# F407.net
KiCad netlist of a schematic drawn in Altium Designer
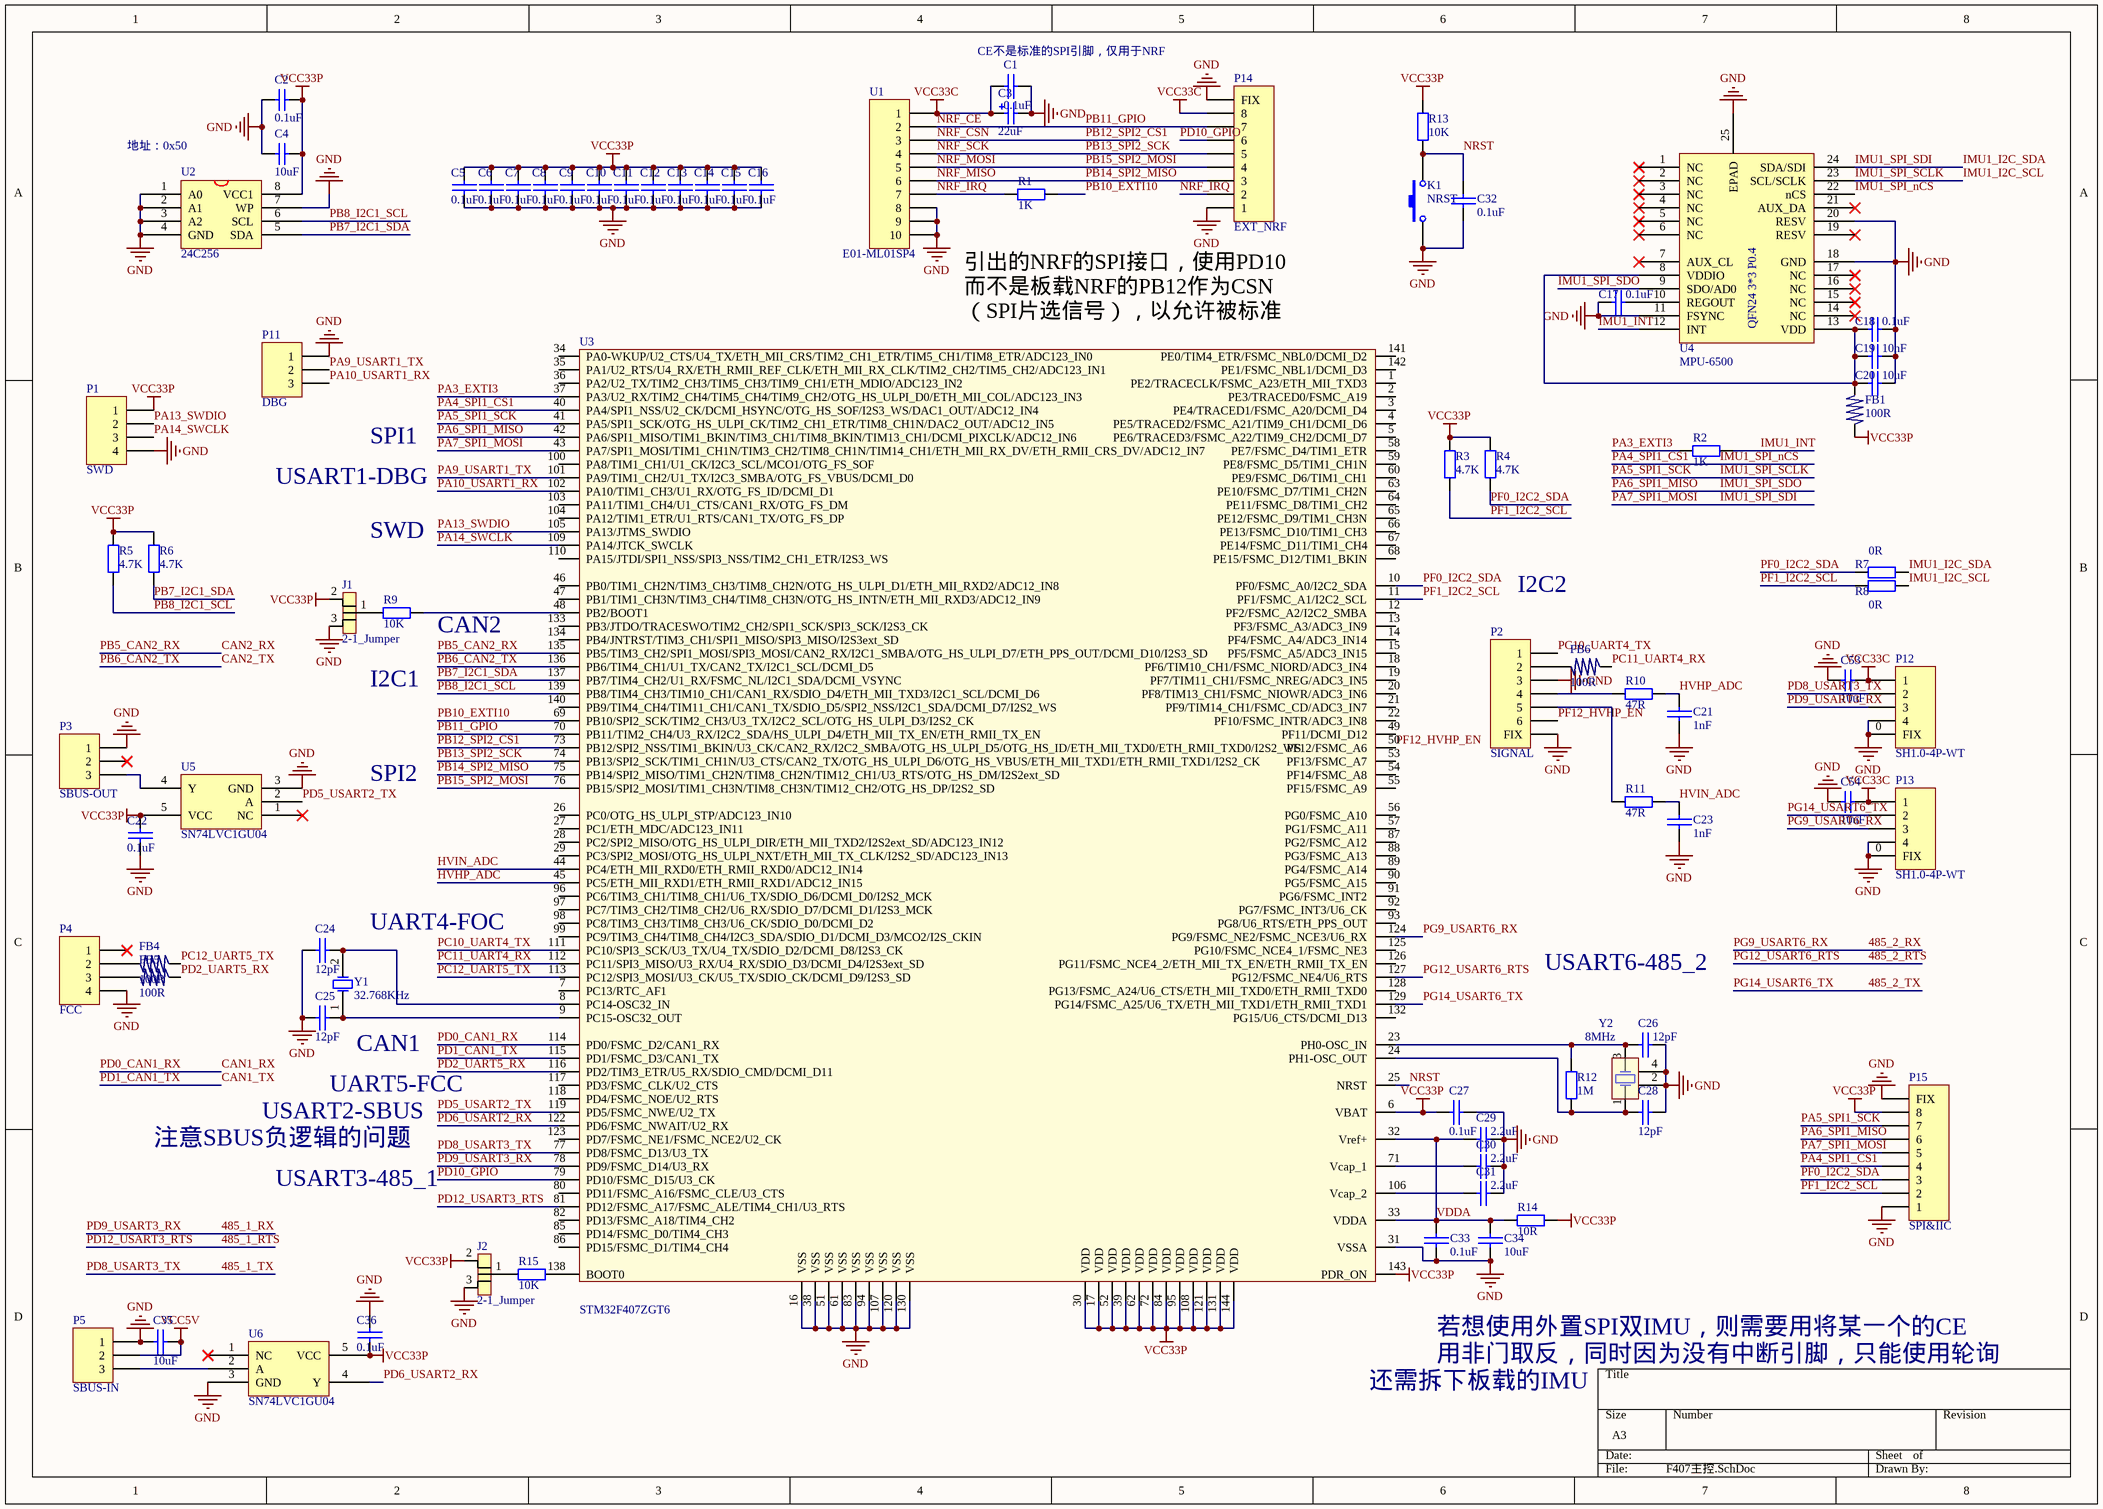
[diagram p0: F407主控.SchDoc]

(export (version "E")
  (design (tool "Eeschema 10.0.6"))
  (components
    (comp (ref "C1")
      (value "0.1uF")
      (footprint "C0805_M")
      (description "Capacitor")
      (libsource (lib "*") (part "CAP"))
    )
    (comp (ref "C2")
      (value "0.1uF")
      (footprint "C0805_M")
      (description "Capacitor")
      (fields (field (name "PUBLISHER") "Altium Limited"))
      (libsource (lib "Miscellaneous Devices") (part "Cap"))
    )
    (comp (ref "C3")
      (value "22uF")
      (footprint "CS 6*6 - R")
      (description "Polarized Capacitor (Axial)")
      (fields (field (name "PUBLISHER") "Altium Limited"))
      (libsource (lib "Miscellaneous Devices") (part "Cap Pol2"))
    )
    (comp (ref "C4")
      (value "10uF")
      (footprint "C0805_M")
      (description "Capacitor")
      (fields (field (name "PUBLISHER") "Altium Limited"))
      (libsource (lib "Miscellaneous Devices") (part "Cap"))
    )
    (comp (ref "C5")
      (value "0.1uF")
      (footprint "C0805_M")
      (description "Capacitor")
      (libsource (lib "*") (part "CAP"))
    )
    (comp (ref "C6")
      (value "0.1uF")
      (footprint "C0805_M")
      (description "Capacitor")
      (libsource (lib "*") (part "CAP"))
    )
    (comp (ref "C7")
      (value "0.1uF")
      (footprint "C0805_M")
      (description "Capacitor")
      (libsource (lib "*") (part "CAP"))
    )
    (comp (ref "C8")
      (value "0.1uF")
      (footprint "C0805_M")
      (description "Capacitor")
      (libsource (lib "*") (part "CAP"))
    )
    (comp (ref "C9")
      (value "0.1uF")
      (footprint "C0805_M")
      (description "Capacitor")
      (libsource (lib "*") (part "CAP"))
    )
    (comp (ref "C10")
      (value "0.1uF")
      (footprint "C0805_M")
      (description "Capacitor")
      (libsource (lib "*") (part "CAP"))
    )
    (comp (ref "C11")
      (value "0.1uF")
      (footprint "C0805_M")
      (description "Capacitor")
      (libsource (lib "*") (part "CAP"))
    )
    (comp (ref "C12")
      (value "0.1uF")
      (footprint "C0805_M")
      (description "Capacitor")
      (libsource (lib "*") (part "CAP"))
    )
    (comp (ref "C13")
      (value "0.1uF")
      (footprint "C0805_M")
      (description "Capacitor")
      (libsource (lib "*") (part "CAP"))
    )
    (comp (ref "C14")
      (value "0.1uF")
      (footprint "C0805_M")
      (description "Capacitor")
      (libsource (lib "*") (part "CAP"))
    )
    (comp (ref "C15")
      (value "0.1uF")
      (footprint "C0805_M")
      (description "Capacitor")
      (libsource (lib "*") (part "CAP"))
    )
    (comp (ref "C16")
      (value "0.1uF")
      (footprint "C0805_M")
      (description "Capacitor")
      (libsource (lib "*") (part "CAP"))
    )
    (comp (ref "C17")
      (value "0.1uF")
      (footprint "C0805_M")
      (description "Capacitor")
      (libsource (lib "*") (part "CAP"))
    )
    (comp (ref "C18")
      (value "0.1uF")
      (footprint "C0805_M")
      (description "Capacitor")
      (libsource (lib "*") (part "CAP"))
    )
    (comp (ref "C19")
      (value "10nF")
      (footprint "C0805_M")
      (description "Capacitor")
      (libsource (lib "*") (part "CAP"))
    )
    (comp (ref "C20")
      (value "10uF")
      (footprint "C0805_M")
      (description "Capacitor")
      (libsource (lib "*") (part "CAP"))
    )
    (comp (ref "C21")
      (value "1nF")
      (footprint "C0805_M")
      (description "Capacitor")
      (libsource (lib "*") (part "CAP"))
    )
    (comp (ref "C22")
      (value "0.1uF")
      (footprint "C0805_M")
      (description "Capacitor")
      (libsource (lib "*") (part "CAP"))
    )
    (comp (ref "C23")
      (value "1nF")
      (footprint "C0805_M")
      (description "Capacitor")
      (libsource (lib "*") (part "CAP"))
    )
    (comp (ref "C24")
      (value "12pF")
      (footprint "C0805_M")
      (description "Capacitor")
      (libsource (lib "*") (part "CAP"))
    )
    (comp (ref "C25")
      (value "12pF")
      (footprint "C0805_M")
      (description "Capacitor")
      (libsource (lib "*") (part "CAP"))
    )
    (comp (ref "C26")
      (value "12pF")
      (footprint "C0805_M")
      (description "Capacitor")
      (libsource (lib "*") (part "CAP"))
    )
    (comp (ref "C27")
      (value "0.1uF")
      (footprint "C0805_M")
      (description "Capacitor")
      (libsource (lib "*") (part "CAP"))
    )
    (comp (ref "C28")
      (value "12pF")
      (footprint "C0805_M")
      (description "Capacitor")
      (libsource (lib "*") (part "CAP"))
    )
    (comp (ref "C29")
      (value "2.2uF")
      (footprint "C0805_M")
      (description "Capacitor")
      (libsource (lib "*") (part "CAP"))
    )
    (comp (ref "C30")
      (value "2.2uF")
      (footprint "C0805_M")
      (description "Capacitor")
      (libsource (lib "*") (part "CAP"))
    )
    (comp (ref "C31")
      (value "2.2uF")
      (footprint "C0805_M")
      (description "Capacitor")
      (libsource (lib "*") (part "CAP"))
    )
    (comp (ref "C32")
      (value "0.1uF")
      (footprint "C0805_M")
      (description "Capacitor")
      (libsource (lib "*") (part "CAP"))
    )
    (comp (ref "C33")
      (value "0.1uF")
      (footprint "C0805_M")
      (description "Capacitor")
      (libsource (lib "*") (part "CAP"))
    )
    (comp (ref "C34")
      (value "10uF")
      (footprint "C0805_M")
      (description "Capacitor")
      (libsource (lib "*") (part "CAP"))
    )
    (comp (ref "C35")
      (value "10uF")
      (footprint "C0805_M")
      (description "Capacitor")
      (libsource (lib "*") (part "CAP"))
    )
    (comp (ref "C36")
      (value "0.1uF")
      (footprint "C0805_M")
      (description "Capacitor")
      (libsource (lib "*") (part "CAP"))
    )
    (comp (ref "C53")
      (value "10uF")
      (footprint "C0805_M")
      (description "Capacitor")
      (fields (field (name "PUBLISHER") "Altium Limited"))
      (libsource (lib "Miscellaneous Devices") (part "Cap"))
    )
    (comp (ref "C54")
      (value "10uF")
      (footprint "C0805_M")
      (description "Capacitor")
      (fields (field (name "PUBLISHER") "Altium Limited"))
      (libsource (lib "Miscellaneous Devices") (part "Cap"))
    )
    (comp (ref "FB1") (value "100R") (footprint "R0805_M") (libsource (lib "EXPLORER") (part "L")))
    (comp (ref "FB4") (value "100R") (footprint "R0805_M") (libsource (lib "") (part "L_1")))
    (comp (ref "FB5") (value "100R") (footprint "R0805_M") (libsource (lib "") (part "L_1")))
    (comp (ref "FB6") (value "100R") (footprint "R0805_M") (libsource (lib "") (part "L_1")))
    (comp (ref "J1")
      (value "2-1_Jumper")
      (footprint "2-1_Jumper")
      (libsource (lib "XL6005") (part "2-1_Jumper"))
    )
    (comp (ref "J2")
      (value "2-1_Jumper")
      (footprint "2-1_Jumper")
      (libsource (lib "XL6005") (part "2-1_Jumper"))
    )
    (comp (ref "K1")
      (value "NRST")
      (footprint "SW_SMT")
      (description "Switch")
      (fields (field (name "PUBLISHER") "Altium Limited"))
      (libsource (lib "Miscellaneous Devices") (part "SW-PB"))
    )
    (comp (ref "P1")
      (value "SWD")
      (footprint "XH2.54-LI-4P")
      (description "Header, 4-Pin")
      (fields (field (name "PUBLISHER") "Altium Limited"))
      (libsource (lib "Miscellaneous Connectors") (part "Header 4"))
    )
    (comp (ref "P2")
      (value "SIGNAL")
      (footprint "SH1.0-LT-6P")
      (description "Header, 7-Pin")
      (fields (field (name "PUBLISHER") "Altium Limited"))
      (libsource (lib "Miscellaneous Connectors") (part "Header 7"))
    )
    (comp (ref "P3")
      (value "SBUS-OUT")
      (footprint "XH2.54-LI-3P")
      (description "Header, 3-Pin")
      (fields (field (name "PUBLISHER") "Altium Limited"))
      (libsource (lib "Miscellaneous Connectors") (part "Header 3"))
    )
    (comp (ref "P4")
      (value "FCC")
      (footprint "XH2.54-LI-4P")
      (description "Header, 4-Pin")
      (fields (field (name "PUBLISHER") "Altium Limited"))
      (libsource (lib "Miscellaneous Connectors") (part "Header 4"))
    )
    (comp (ref "P5")
      (value "SBUS-IN")
      (footprint "XH2.54-LI-3P")
      (description "Header, 3-Pin")
      (fields (field (name "PUBLISHER") "Altium Limited"))
      (libsource (lib "Miscellaneous Connectors") (part "Header 3"))
    )
    (comp (ref "P11")
      (value "DBG")
      (footprint "XH2.54-LI-3P")
      (description "Header, 3-Pin")
      (fields (field (name "PUBLISHER") "Altium Limited"))
      (libsource (lib "Miscellaneous Connectors") (part "Header 3"))
    )
    (comp (ref "P12")
      (value "SH1.0-4P-WT")
      (footprint "SH1.0-WT-4P")
      (description "Header, 5-Pin")
      (fields (field (name "PUBLISHER") "Altium Limited"))
      (libsource (lib "Miscellaneous Connectors") (part "Header 5"))
    )
    (comp (ref "P13")
      (value "SH1.0-4P-WT")
      (footprint "SH1.0-WT-4P")
      (description "Header, 5-Pin")
      (fields (field (name "PUBLISHER") "Altium Limited"))
      (libsource (lib "Miscellaneous Connectors") (part "Header 5"))
    )
    (comp (ref "P14")
      (value "EXT_NRF")
      (footprint "SH1.0-WT-8P")
      (description "Header, 9-Pin")
      (fields (field (name "PUBLISHER") "Altium Limited"))
      (libsource (lib "Miscellaneous Connectors") (part "Header 9"))
    )
    (comp (ref "P15")
      (value "SPI&IIC")
      (footprint "SH1.0-WT-8P")
      (description "Header, 9-Pin")
      (fields (field (name "PUBLISHER") "Altium Limited"))
      (libsource (lib "Miscellaneous Connectors") (part "Header 9"))
    )
    (comp (ref "R1")
      (value "1K")
      (footprint "R0805_M")
      (description "Resistor")
      (fields (field (name "PUBLISHER") "Altium Limited"))
      (libsource (lib "") (part "Res2_1"))
    )
    (comp (ref "R2")
      (value "1K")
      (footprint "R0805_M")
      (description "Resistor")
      (fields (field (name "PUBLISHER") "Altium Limited"))
      (libsource (lib "") (part "Res2_1"))
    )
    (comp (ref "R3")
      (value "4.7K")
      (footprint "R0805_M")
      (description "Resistor")
      (fields (field (name "PUBLISHER") "Altium Limited"))
      (libsource (lib "") (part "Res2_2"))
    )
    (comp (ref "R4")
      (value "4.7K")
      (footprint "R0805_M")
      (description "Resistor")
      (fields (field (name "PUBLISHER") "Altium Limited"))
      (libsource (lib "") (part "Res2_2"))
    )
    (comp (ref "R5")
      (value "4.7K")
      (footprint "R0805_M")
      (description "Resistor")
      (fields (field (name "PUBLISHER") "Altium Limited"))
      (libsource (lib "") (part "Res2_2"))
    )
    (comp (ref "R6")
      (value "4.7K")
      (footprint "R0805_M")
      (description "Resistor")
      (fields (field (name "PUBLISHER") "Altium Limited"))
      (libsource (lib "") (part "Res2_2"))
    )
    (comp (ref "R7")
      (value "0R")
      (footprint "R0805_M")
      (description "Resistor")
      (fields (field (name "PUBLISHER") "Altium Limited"))
      (libsource (lib "") (part "Res2_1"))
    )
    (comp (ref "R8")
      (value "0R")
      (footprint "R0805_M")
      (description "Resistor")
      (fields (field (name "PUBLISHER") "Altium Limited"))
      (libsource (lib "") (part "Res2_1"))
    )
    (comp (ref "R9")
      (value "10K")
      (footprint "R0805_M")
      (description "Resistor")
      (fields (field (name "PUBLISHER") "Altium Limited"))
      (libsource (lib "") (part "Res2_1"))
    )
    (comp (ref "R10")
      (value "47R")
      (footprint "R0805_M")
      (description "Resistor")
      (fields (field (name "PUBLISHER") "Altium Limited"))
      (libsource (lib "Miscellaneous Devices") (part "Res2"))
    )
    (comp (ref "R11")
      (value "47R")
      (footprint "R0805_M")
      (description "Resistor")
      (fields (field (name "PUBLISHER") "Altium Limited"))
      (libsource (lib "Miscellaneous Devices") (part "Res2"))
    )
    (comp (ref "R12")
      (value "1M")
      (footprint "R0805_M")
      (description "Resistor")
      (fields (field (name "PUBLISHER") "Altium Limited"))
      (libsource (lib "") (part "Res2_3"))
    )
    (comp (ref "R13")
      (value "10K")
      (footprint "R0805_M")
      (description "Resistor")
      (fields (field (name "PUBLISHER") "Altium Limited"))
      (libsource (lib "") (part "Res2_2"))
    )
    (comp (ref "R14")
      (value "10R")
      (footprint "R0805_M")
      (description "Resistor")
      (fields (field (name "PUBLISHER") "Altium Limited"))
      (libsource (lib "") (part "Res2_1"))
    )
    (comp (ref "R15")
      (value "10K")
      (footprint "R0805_M")
      (description "Resistor")
      (fields (field (name "PUBLISHER") "Altium Limited"))
      (libsource (lib "") (part "Res2_1"))
    )
    (comp (ref "U1")
      (value "E01-ML01SP4")
      (footprint "PE01-ML01SP4")
      (description "Header, 10-Pin")
      (fields (field (name "PUBLISHER") "Altium Limited"))
      (libsource (lib "Miscellaneous Connectors") (part "Header 10"))
    )
    (comp (ref "U2")
      (value "24C256")
      (footprint "SOP-8")
      (libsource (lib "Explorer STM32F407封装库") (part "24C256"))
    )
    (comp (ref "U3")
      (value "STM32F407ZGT6")
      (footprint "2.12-矩形QFP封装:LQFP144")
      (description "STM32F407ZET6")
      (libsource (lib "EXPLORER") (part "STM32F407ZET6"))
    )
    (comp (ref "U4")
      (value "MPU-6500")
      (footprint "QFN24-L3.0-W3.0-P0.4")
      (description "6 DoF IMU Footprint QFN24 3*3 P0.4")
      (libsource (lib "XL6005") (part "MPU-6500"))
    )
    (comp (ref "U5")
      (value "SN74LVC1GU04")
      (footprint "SOT-23-5")
      (libsource (lib "") (part "SN74LVC1GU04_1"))
    )
    (comp (ref "U6")
      (value "SN74LVC1GU04")
      (footprint "SOT-23-5")
      (libsource (lib "7688A原理图封装") (part "SN74LVC1GU04"))
    )
    (comp (ref "Y1")
      (value "32.768KHz")
      (footprint "OSC-3215-2P")
      (description "CL=12.5pF")
      (fields (field (name "PUBLISHER") "Altium Limited"))
      (libsource (lib "Miscellaneous Devices") (part "XTAL"))
    )
    (comp (ref "Y2")
      (value "8MHz")
      (footprint "1.09-晶振、晶体:OSC-3225-4P")
      (description "CL=12pF")
      (fields (field (name "PUBLISHER") "Altium Limited"))
      (libsource (lib "XL6005") (part "XTAL-4"))
    )
  )
  (nets
    (net (code "1") (name "/485_1_RTS") (class "Default")
      (node (ref "U3") (pin "81") (pinfunction "PD12/FSMC_A17/FSMC_ALE/TIM4_CH1/U3_RTS_81") (pintype "passive"))
    )
    (net (code "2") (name "/485_1_RX") (class "Default")
      (node (ref "P12") (pin "3") (pinfunction "3_3") (pintype "passive"))
      (node (ref "U3") (pin "78") (pinfunction "PD9/FSMC_D14/U3_RX_78") (pintype "passive"))
    )
    (net (code "3") (name "/485_1_TX") (class "Default")
      (node (ref "P12") (pin "2") (pinfunction "2_2") (pintype "passive"))
      (node (ref "U3") (pin "77") (pinfunction "PD8/FSMC_D13/U3_TX_77") (pintype "passive"))
    )
    (net (code "4") (name "/485_2_RTS") (class "Default")
      (node (ref "U3") (pin "127") (pinfunction "PG12/FSMC_NE4/U6_RTS_127") (pintype "passive"))
    )
    (net (code "5") (name "/485_2_RX") (class "Default")
      (node (ref "P13") (pin "3") (pinfunction "3_3") (pintype "passive"))
      (node (ref "U3") (pin "124") (pinfunction "PG9/FSMC_NE2/FSMC_NCE3/U6_RX_124") (pintype "passive"))
    )
    (net (code "6") (name "/485_2_TX") (class "Default")
      (node (ref "P13") (pin "2") (pinfunction "2_2") (pintype "passive"))
      (node (ref "U3") (pin "129") (pinfunction "PG14/FSMC_A25/U6_TX/ETH_MII_TXD1/ETH_RMII_TXD1_129") (pintype "passive"))
    )
    (net (code "7") (name "/CAN1_RX") (class "Default")
      (node (ref "U3") (pin "114") (pinfunction "PD0/FSMC_D2/CAN1_RX_114") (pintype "passive"))
    )
    (net (code "8") (name "/CAN1_TX") (class "Default")
      (node (ref "U3") (pin "115") (pinfunction "PD1/FSMC_D3/CAN1_TX_115") (pintype "passive"))
    )
    (net (code "9") (name "/CAN2_RX") (class "Default")
      (node (ref "U3") (pin "135") (pinfunction "PB5/TIM3_CH2/SPI1_MOSI/SPI3_MOSI/CAN2_RX/I2C1_SMBA/OTG_HS_ULPI_D7/ETH_PPS_OUT/DCMI_D10/I2S3_SD_135") (pintype "passive"))
    )
    (net (code "10") (name "/CAN2_TX") (class "Default")
      (node (ref "U3") (pin "136") (pinfunction "PB6/TIM4_CH1/U1_TX/CAN2_TX/I2C1_SCL/DCMI_D5_136") (pintype "passive"))
    )
    (net (code "11") (name "/HVHP_ADC") (class "Default")
      (node (ref "C21") (pin "2") (pinfunction "2_2") (pintype "passive"))
      (node (ref "R10") (pin "2") (pinfunction "2_2") (pintype "passive"))
      (node (ref "U3") (pin "45") (pinfunction "PC5/ETH_MII_RXD1/ETH_RMII_RXD1/ADC12_IN15_45") (pintype "passive"))
    )
    (net (code "12") (name "/HVIN_ADC") (class "Default")
      (node (ref "C23") (pin "2") (pinfunction "2_2") (pintype "passive"))
      (node (ref "R11") (pin "2") (pinfunction "2_2") (pintype "passive"))
      (node (ref "U3") (pin "44") (pinfunction "PC4/ETH_MII_RXD0/ETH_RMII_RXD0/ADC12_IN14_44") (pintype "passive"))
    )
    (net (code "13") (name "/IMU1_I2C_SCL") (class "Default")
      (node (ref "P15") (pin "7") (pinfunction "7_7") (pintype "passive"))
      (node (ref "R8") (pin "1") (pinfunction "1_1") (pintype "passive"))
      (node (ref "U3") (pin "41") (pinfunction "PA5/SPI1_SCK/OTG_HS_ULPI_CK/TIM2_CH1_ETR/TIM8_CH1N/DAC2_OUT/ADC12_IN5_41") (pintype "passive"))
      (node (ref "U4") (pin "23") (pinfunction "SCL/SCLK_23") (pintype "passive"))
    )
    (net (code "14") (name "/IMU1_I2C_SDA") (class "Default")
      (node (ref "P15") (pin "5") (pinfunction "5_5") (pintype "passive"))
      (node (ref "R7") (pin "1") (pinfunction "1_1") (pintype "passive"))
      (node (ref "U3") (pin "43") (pinfunction "PA7/SPI1_MOSI/TIM1_CH1N/TIM3_CH2/TIM8_CH1N/TIM14_CH1/ETH_MII_RX_DV/ETH_RMII_CRS_DV/ADC12_IN7_43") (pintype "passive"))
      (node (ref "U4") (pin "24") (pinfunction "SDA/SDI_24") (pintype "passive"))
    )
    (net (code "15") (name "/IMU1_INT") (class "Default")
      (node (ref "R2") (pin "1") (pinfunction "1_1") (pintype "passive"))
      (node (ref "U4") (pin "12") (pinfunction "INT_12") (pintype "passive"))
    )
    (net (code "16") (name "/IMU1_SPI_SDO") (class "Default")
      (node (ref "P15") (pin "6") (pinfunction "6_6") (pintype "passive"))
      (node (ref "U3") (pin "42") (pinfunction "PA6/SPI1_MISO/TIM1_BKIN/TIM3_CH1/TIM8_BKIN/TIM13_CH1/DCMI_PIXCLK/ADC12_IN6_42") (pintype "passive"))
      (node (ref "U4") (pin "9") (pinfunction "SDO/AD0_9") (pintype "passive"))
    )
    (net (code "17") (name "/IMU1_SPI_nCS") (class "Default")
      (node (ref "P15") (pin "4") (pinfunction "4_4") (pintype "passive"))
      (node (ref "U3") (pin "40") (pinfunction "PA4/SPI1_NSS/U2_CK/DCMI_HSYNC/OTG_HS_SOF/I2S3_WS/DAC1_OUT/ADC12_IN4_40") (pintype "passive"))
      (node (ref "U4") (pin "22") (pinfunction "nCS_22") (pintype "passive"))
    )
    (net (code "18") (name "/NRF_CE") (class "Default")
      (node (ref "P14") (pin "7") (pinfunction "7_7") (pintype "passive"))
      (node (ref "U1") (pin "2") (pinfunction "2_2") (pintype "passive"))
      (node (ref "U3") (pin "70") (pinfunction "PB11/TIM2_CH4/U3_RX/I2C2_SDA/HS_ULPI_D4/ETH_MII_TX_EN/ETH_RMII_TX_EN_70") (pintype "passive"))
    )
    (net (code "19") (name "/NRF_CSN") (class "Default")
      (node (ref "U1") (pin "3") (pinfunction "3_3") (pintype "passive"))
      (node (ref "U3") (pin "73") (pinfunction "PB12/SPI2_NSS/TIM1_BKIN/U3_CK/CAN2_RX/I2C2_SMBA/OTG_HS_ULPI_D5/OTG_HS_ID/ETH_MII_TXD0/ETH_RMII_TXD0/I2S2_WS_73") (pintype "passive"))
    )
    (net (code "20") (name "/NRF_IRQ") (class "Default")
      (node (ref "P14") (pin "2") (pinfunction "2_2") (pintype "passive"))
      (node (ref "R1") (pin "2") (pinfunction "2_2") (pintype "passive"))
      (node (ref "U1") (pin "7") (pinfunction "7_7") (pintype "passive"))
    )
    (net (code "21") (name "/NRF_MISO") (class "Default")
      (node (ref "P14") (pin "3") (pinfunction "3_3") (pintype "passive"))
      (node (ref "U1") (pin "6") (pinfunction "6_6") (pintype "passive"))
      (node (ref "U3") (pin "75") (pinfunction "PB14/SPI2_MISO/TIM1_CH2N/TIM8_CH2N/TIM12_CH1/U3_RTS/OTG_HS_DM/I2S2ext_SD_75") (pintype "passive"))
    )
    (net (code "22") (name "/NRF_MOSI") (class "Default")
      (node (ref "P14") (pin "4") (pinfunction "4_4") (pintype "passive"))
      (node (ref "U1") (pin "5") (pinfunction "5_5") (pintype "passive"))
      (node (ref "U3") (pin "76") (pinfunction "PB15/SPI2_MOSI/TIM1_CH3N/TIM8_CH3N/TIM12_CH2/OTG_HS_DP/I2S2_SD_76") (pintype "passive"))
    )
    (net (code "23") (name "/NRF_SCK") (class "Default")
      (node (ref "P14") (pin "5") (pinfunction "5_5") (pintype "passive"))
      (node (ref "U1") (pin "4") (pinfunction "4_4") (pintype "passive"))
      (node (ref "U3") (pin "74") (pinfunction "PB13/SPI2_SCK/TIM1_CH1N/U3_CTS/CAN2_TX/OTG_HS_ULPI_D6/OTG_HS_VBUS/ETH_MII_TXD1/ETH_RMII_TXD1/I2S2_CK_74") (pintype "passive"))
    )
    (net (code "24") (name "/NRST") (class "Default")
      (node (ref "C32") (pin "2") (pinfunction "2_2") (pintype "passive"))
      (node (ref "K1") (pin "2") (pinfunction "2_2") (pintype "passive"))
      (node (ref "R13") (pin "2") (pinfunction "2_2") (pintype "passive"))
      (node (ref "U3") (pin "25") (pinfunction "NRST_25") (pintype "passive"))
    )
    (net (code "25") (name "/PA3_EXTI3") (class "Default")
      (node (ref "R2") (pin "2") (pinfunction "2_2") (pintype "passive"))
      (node (ref "U3") (pin "37") (pinfunction "PA3/U2_RX/TIM2_CH4/TIM5_CH4/TIM9_CH2/OTG_HS_ULPI_D0/ETH_MII_COL/ADC123_IN3_37") (pintype "passive"))
    )
    (net (code "26") (name "/PA9_USART1_TX") (class "Default")
      (node (ref "P11") (pin "2") (pinfunction "2_2") (pintype "passive"))
      (node (ref "U3") (pin "101") (pinfunction "PA9/TIM1_CH2/U1_TX/I2C3_SMBA/OTG_FS_VBUS/DCMI_D0_101") (pintype "passive"))
    )
    (net (code "27") (name "/PA10_USART1_RX") (class "Default")
      (node (ref "P11") (pin "3") (pinfunction "3_3") (pintype "passive"))
      (node (ref "U3") (pin "102") (pinfunction "PA10/TIM1_CH3/U1_RX/OTG_FS_ID/DCMI_D1_102") (pintype "passive"))
    )
    (net (code "28") (name "/PA13_SWDIO") (class "Default")
      (node (ref "P1") (pin "2") (pinfunction "2_2") (pintype "passive"))
      (node (ref "U3") (pin "105") (pinfunction "PA13/JTMS_SWDIO_105") (pintype "passive"))
    )
    (net (code "29") (name "/PA14_SWCLK") (class "Default")
      (node (ref "P1") (pin "3") (pinfunction "3_3") (pintype "passive"))
      (node (ref "U3") (pin "109") (pinfunction "PA14/JTCK_SWCLK_109") (pintype "passive"))
    )
    (net (code "30") (name "/PB7_I2C1_SDA") (class "Default")
      (node (ref "R6") (pin "2") (pinfunction "2_2") (pintype "passive"))
      (node (ref "U2") (pin "5") (pinfunction "SDA_5") (pintype "passive"))
      (node (ref "U3") (pin "137") (pinfunction "PB7/TIM4_CH2/U1_RX/FSMC_NL/I2C1_SDA/DCMI_VSYNC_137") (pintype "passive"))
    )
    (net (code "31") (name "/PB8_I2C1_SCL") (class "Default")
      (node (ref "R5") (pin "2") (pinfunction "2_2") (pintype "passive"))
      (node (ref "U2") (pin "6") (pinfunction "SCL_6") (pintype "passive"))
      (node (ref "U3") (pin "139") (pinfunction "PB8/TIM4_CH3/TIM10_CH1/CAN1_RX/SDIO_D4/ETH_MII_TXD3/I2C1_SCL/DCMI_D6_139") (pintype "passive"))
    )
    (net (code "32") (name "/PB10_EXTI10") (class "Default")
      (node (ref "R1") (pin "1") (pinfunction "1_1") (pintype "passive"))
      (node (ref "U3") (pin "69") (pinfunction "PB10/SPI2_SCK/TIM2_CH3/U3_TX/I2C2_SCL/OTG_HS_ULPI_D3/I2S2_CK_69") (pintype "passive"))
    )
    (net (code "33") (name "/PC10_UART4_TX") (class "Default")
      (node (ref "P2") (pin "1") (pinfunction "1_1") (pintype "passive"))
      (node (ref "U3") (pin "111") (pinfunction "PC10/SPI3_SCK/U3_TX/U4_TX/SDIO_D2/DCMI_D8/I2S3_CK_111") (pintype "passive"))
    )
    (net (code "34") (name "/PC11_UART4_RX") (class "Default")
      (node (ref "FB6") (pin "1") (pintype "passive"))
      (node (ref "U3") (pin "112") (pinfunction "PC11/SPI3_MISO/U3_RX/U4_RX/SDIO_D3/DCMI_D4/I2S3ext_SD_112") (pintype "passive"))
    )
    (net (code "35") (name "/PC12_UART5_TX") (class "Default")
      (node (ref "FB4") (pin "1") (pintype "passive"))
      (node (ref "U3") (pin "113") (pinfunction "PC12/SPI3_MOSI/U3_CK/U5_TX/SDIO_CK/DCMI_D9/I2S3_SD_113") (pintype "passive"))
    )
    (net (code "36") (name "/PD2_UART5_RX") (class "Default")
      (node (ref "FB5") (pin "1") (pintype "passive"))
      (node (ref "U3") (pin "116") (pinfunction "PD2/TIM3_ETR/U5_RX/SDIO_CMD/DCMI_D11_116") (pintype "passive"))
    )
    (net (code "37") (name "/PD5_USART2_TX") (class "Default")
      (node (ref "U3") (pin "119") (pinfunction "PD5/FSMC_NWE/U2_TX_119") (pintype "passive"))
      (node (ref "U5") (pin "2") (pinfunction "A_2") (pintype "passive"))
    )
    (net (code "38") (name "/PD6_USART2_RX") (class "Default")
      (node (ref "U3") (pin "122") (pinfunction "PD6/FSMC_NWAIT/U2_RX_122") (pintype "passive"))
      (node (ref "U6") (pin "4") (pinfunction "Y_4") (pintype "passive"))
    )
    (net (code "39") (name "/PD10_GPIO") (class "Default")
      (node (ref "P14") (pin "6") (pinfunction "6_6") (pintype "passive"))
      (node (ref "U3") (pin "79") (pinfunction "PD10/FSMC_D15/U3_CK_79") (pintype "passive"))
    )
    (net (code "40") (name "/PF0_I2C2_SDA") (class "Default")
      (node (ref "P15") (pin "3") (pinfunction "3_3") (pintype "passive"))
      (node (ref "R4") (pin "2") (pinfunction "2_2") (pintype "passive"))
      (node (ref "R7") (pin "2") (pinfunction "2_2") (pintype "passive"))
      (node (ref "U3") (pin "10") (pinfunction "PF0/FSMC_A0/I2C2_SDA_10") (pintype "passive"))
    )
    (net (code "41") (name "/PF1_I2C2_SCL") (class "Default")
      (node (ref "P15") (pin "2") (pinfunction "2_2") (pintype "passive"))
      (node (ref "R3") (pin "2") (pinfunction "2_2") (pintype "passive"))
      (node (ref "R8") (pin "2") (pinfunction "2_2") (pintype "passive"))
      (node (ref "U3") (pin "11") (pinfunction "PF1/FSMC_A1/I2C2_SCL_11") (pintype "passive"))
    )
    (net (code "42") (name "/PF12_HVHP_EN") (class "Default")
      (node (ref "P2") (pin "6") (pinfunction "6_6") (pintype "passive"))
      (node (ref "U3") (pin "50") (pinfunction "PF12/FSMC_A6_50") (pintype "passive"))
    )
    (net (code "43") (name "/VDDA") (class "Default")
      (node (ref "C29") (pin "1") (pinfunction "1_1") (pintype "passive"))
      (node (ref "C33") (pin "2") (pinfunction "2_2") (pintype "passive"))
      (node (ref "C34") (pin "2") (pinfunction "2_2") (pintype "passive"))
      (node (ref "R14") (pin "2") (pinfunction "2_2") (pintype "passive"))
      (node (ref "U3") (pin "32") (pinfunction "Vref+_32") (pintype "passive"))
      (node (ref "U3") (pin "33") (pinfunction "VDDA_33") (pintype "passive"))
    )
    (net (code "44") (name "GND") (class "Default")
      (node (ref "C1") (pin "1") (pinfunction "1_1") (pintype "passive"))
      (node (ref "C10") (pin "1") (pinfunction "1_1") (pintype "passive"))
      (node (ref "C11") (pin "1") (pinfunction "1_1") (pintype "passive"))
      (node (ref "C12") (pin "1") (pinfunction "1_1") (pintype "passive"))
      (node (ref "C13") (pin "1") (pinfunction "1_1") (pintype "passive"))
      (node (ref "C14") (pin "1") (pinfunction "1_1") (pintype "passive"))
      (node (ref "C15") (pin "1") (pinfunction "1_1") (pintype "passive"))
      (node (ref "C16") (pin "1") (pinfunction "1_1") (pintype "passive"))
      (node (ref "C17") (pin "2") (pinfunction "2_2") (pintype "passive"))
      (node (ref "C18") (pin "1") (pinfunction "1_1") (pintype "passive"))
      (node (ref "C19") (pin "1") (pinfunction "1_1") (pintype "passive"))
      (node (ref "C2") (pin "1") (pinfunction "1_1") (pintype "passive"))
      (node (ref "C20") (pin "1") (pinfunction "1_1") (pintype "passive"))
      (node (ref "C21") (pin "1") (pinfunction "1_1") (pintype "passive"))
      (node (ref "C22") (pin "1") (pinfunction "1_1") (pintype "passive"))
      (node (ref "C23") (pin "1") (pinfunction "1_1") (pintype "passive"))
      (node (ref "C24") (pin "1") (pinfunction "1_1") (pintype "passive"))
      (node (ref "C25") (pin "1") (pinfunction "1_1") (pintype "passive"))
      (node (ref "C26") (pin "2") (pinfunction "2_2") (pintype "passive"))
      (node (ref "C27") (pin "1") (pinfunction "1_1") (pintype "passive"))
      (node (ref "C28") (pin "2") (pinfunction "2_2") (pintype "passive"))
      (node (ref "C29") (pin "2") (pinfunction "2_2") (pintype "passive"))
      (node (ref "C3") (pin "2") (pinfunction "2_2") (pintype "passive"))
      (node (ref "C30") (pin "2") (pinfunction "2_2") (pintype "passive"))
      (node (ref "C31") (pin "2") (pinfunction "2_2") (pintype "passive"))
      (node (ref "C32") (pin "1") (pinfunction "1_1") (pintype "passive"))
      (node (ref "C33") (pin "1") (pinfunction "1_1") (pintype "passive"))
      (node (ref "C34") (pin "1") (pinfunction "1_1") (pintype "passive"))
      (node (ref "C35") (pin "2") (pinfunction "2_2") (pintype "passive"))
      (node (ref "C36") (pin "2") (pinfunction "2_2") (pintype "passive"))
      (node (ref "C4") (pin "1") (pinfunction "1_1") (pintype "passive"))
      (node (ref "C5") (pin "1") (pinfunction "1_1") (pintype "passive"))
      (node (ref "C53") (pin "1") (pinfunction "1_1") (pintype "passive"))
      (node (ref "C54") (pin "1") (pinfunction "1_1") (pintype "passive"))
      (node (ref "C6") (pin "1") (pinfunction "1_1") (pintype "passive"))
      (node (ref "C7") (pin "1") (pinfunction "1_1") (pintype "passive"))
      (node (ref "C8") (pin "1") (pinfunction "1_1") (pintype "passive"))
      (node (ref "C9") (pin "1") (pinfunction "1_1") (pintype "passive"))
      (node (ref "J1") (pin "3") (pintype "passive"))
      (node (ref "J2") (pin "3") (pintype "passive"))
      (node (ref "K1") (pin "1") (pinfunction "1_1") (pintype "passive"))
      (node (ref "P1") (pin "4") (pinfunction "4_4") (pintype "passive"))
      (node (ref "P11") (pin "1") (pinfunction "1_1") (pintype "passive"))
      (node (ref "P12") (pin "0") (pinfunction "FIX_0") (pintype "passive"))
      (node (ref "P12") (pin "4") (pinfunction "4_4") (pintype "passive"))
      (node (ref "P13") (pin "0") (pinfunction "FIX_0") (pintype "passive"))
      (node (ref "P13") (pin "4") (pinfunction "4_4") (pintype "passive"))
      (node (ref "P14") (pin "0") (pinfunction "FIX_0") (pintype "passive"))
      (node (ref "P14") (pin "1") (pinfunction "1_1") (pintype "passive"))
      (node (ref "P15") (pin "0") (pinfunction "FIX_0") (pintype "passive"))
      (node (ref "P15") (pin "1") (pinfunction "1_1") (pintype "passive"))
      (node (ref "P2") (pin "0") (pinfunction "FIX_0") (pintype "passive"))
      (node (ref "P2") (pin "3") (pinfunction "3_3") (pintype "passive"))
      (node (ref "P3") (pin "1") (pinfunction "1_1") (pintype "passive"))
      (node (ref "P4") (pin "4") (pinfunction "4_4") (pintype "passive"))
      (node (ref "P5") (pin "1") (pinfunction "1_1") (pintype "passive"))
      (node (ref "U1") (pin "10") (pinfunction "10_10") (pintype "passive"))
      (node (ref "U1") (pin "8") (pinfunction "8_8") (pintype "passive"))
      (node (ref "U1") (pin "9") (pinfunction "9_9") (pintype "passive"))
      (node (ref "U2") (pin "1") (pinfunction "A0_1") (pintype "passive"))
      (node (ref "U2") (pin "2") (pinfunction "A1_2") (pintype "passive"))
      (node (ref "U2") (pin "3") (pinfunction "A2_3") (pintype "passive"))
      (node (ref "U2") (pin "4") (pinfunction "GND_4") (pintype "passive"))
      (node (ref "U2") (pin "7") (pinfunction "WP_7") (pintype "passive"))
      (node (ref "U3") (pin "107") (pinfunction "VSS_107") (pintype "passive"))
      (node (ref "U3") (pin "120") (pinfunction "VSS_120") (pintype "passive"))
      (node (ref "U3") (pin "130") (pinfunction "VSS_130") (pintype "passive"))
      (node (ref "U3") (pin "16") (pinfunction "VSS_16") (pintype "passive"))
      (node (ref "U3") (pin "31") (pinfunction "VSSA_31") (pintype "passive"))
      (node (ref "U3") (pin "38") (pinfunction "VSS_38") (pintype "passive"))
      (node (ref "U3") (pin "51") (pinfunction "VSS_51") (pintype "passive"))
      (node (ref "U3") (pin "61") (pinfunction "VSS_61") (pintype "passive"))
      (node (ref "U3") (pin "83") (pinfunction "VSS_83") (pintype "passive"))
      (node (ref "U3") (pin "94") (pinfunction "VSS_94") (pintype "passive"))
      (node (ref "U4") (pin "11") (pinfunction "FSYNC_11") (pintype "passive"))
      (node (ref "U4") (pin "18") (pinfunction "GND_18") (pintype "passive"))
      (node (ref "U4") (pin "20") (pinfunction "RESV_20") (pintype "passive"))
      (node (ref "U4") (pin "25") (pinfunction "EPAD_25") (pintype "passive"))
      (node (ref "U5") (pin "3") (pinfunction "GND_3") (pintype "passive"))
      (node (ref "U6") (pin "3") (pinfunction "GND_3") (pintype "passive"))
      (node (ref "Y2") (pin "2") (pinfunction "GND_2") (pintype "passive"))
      (node (ref "Y2") (pin "4") (pinfunction "GND_4") (pintype "passive"))
    )
    (net (code "45") (name "Net-(FB4-Pad2)") (class "Default")
      (node (ref "FB4") (pin "2") (pintype "passive"))
      (node (ref "P4") (pin "2") (pinfunction "2_2") (pintype "passive"))
    )
    (net (code "46") (name "Net-(FB5-Pad2)") (class "Default")
      (node (ref "FB5") (pin "2") (pintype "passive"))
      (node (ref "P4") (pin "3") (pinfunction "3_3") (pintype "passive"))
    )
    (net (code "47") (name "Net-(FB6-Pad2)") (class "Default")
      (node (ref "FB6") (pin "2") (pintype "passive"))
      (node (ref "P2") (pin "2") (pinfunction "2_2") (pintype "passive"))
    )
    (net (code "48") (name "Net-(J1-Pad1)") (class "Default")
      (node (ref "J1") (pin "1") (pintype "passive"))
      (node (ref "R9") (pin "2") (pinfunction "2_2") (pintype "passive"))
    )
    (net (code "49") (name "Net-(J2-Pad1)") (class "Default")
      (node (ref "J2") (pin "1") (pintype "passive"))
      (node (ref "R15") (pin "2") (pinfunction "2_2") (pintype "passive"))
    )
    (net (code "50") (name "Net-(P2-Pad4)") (class "Default")
      (node (ref "P2") (pin "4") (pinfunction "4_4") (pintype "passive"))
      (node (ref "R10") (pin "1") (pinfunction "1_1") (pintype "passive"))
    )
    (net (code "51") (name "Net-(P2-Pad5)") (class "Default")
      (node (ref "P2") (pin "5") (pinfunction "5_5") (pintype "passive"))
      (node (ref "R11") (pin "1") (pinfunction "1_1") (pintype "passive"))
    )
    (net (code "52") (name "Net-(U3-BOOT0)") (class "Default")
      (node (ref "R15") (pin "1") (pinfunction "1_1") (pintype "passive"))
      (node (ref "U3") (pin "138") (pinfunction "BOOT0_138") (pintype "passive"))
    )
    (net (code "53") (name "Net-(U3-PB2{slash}BOOT1)") (class "Default")
      (node (ref "R9") (pin "1") (pinfunction "1_1") (pintype "passive"))
      (node (ref "U3") (pin "48") (pinfunction "PB2/BOOT1_48") (pintype "passive"))
    )
    (net (code "54") (name "Net-(U3-PC14-OSC32_IN)") (class "Default")
      (node (ref "C24") (pin "2") (pinfunction "2_2") (pintype "passive"))
      (node (ref "U3") (pin "8") (pinfunction "PC14-OSC32_IN_8") (pintype "passive"))
      (node (ref "Y1") (pin "2") (pinfunction "OSC2_2") (pintype "passive"))
    )
    (net (code "55") (name "Net-(U3-PC15-OSC32_OUT)") (class "Default")
      (node (ref "C25") (pin "2") (pinfunction "2_2") (pintype "passive"))
      (node (ref "U3") (pin "9") (pinfunction "PC15-OSC32_OUT_9") (pintype "passive"))
      (node (ref "Y1") (pin "1") (pinfunction "OSC1_1") (pintype "passive"))
    )
    (net (code "56") (name "Net-(U3-PH0-OSC_IN)") (class "Default")
      (node (ref "C26") (pin "1") (pinfunction "1_1") (pintype "passive"))
      (node (ref "R12") (pin "2") (pinfunction "2_2") (pintype "passive"))
      (node (ref "U3") (pin "23") (pinfunction "PH0-OSC_IN_23") (pintype "passive"))
      (node (ref "Y2") (pin "3") (pinfunction "OSC2_3") (pintype "passive"))
    )
    (net (code "57") (name "Net-(U3-PH1-OSC_OUT)") (class "Default")
      (node (ref "C28") (pin "1") (pinfunction "1_1") (pintype "passive"))
      (node (ref "R12") (pin "1") (pinfunction "1_1") (pintype "passive"))
      (node (ref "U3") (pin "24") (pinfunction "PH1-OSC_OUT_24") (pintype "passive"))
      (node (ref "Y2") (pin "1") (pinfunction "OSC1_1") (pintype "passive"))
    )
    (net (code "58") (name "Net-(U3-Vcap_1)") (class "Default")
      (node (ref "C30") (pin "1") (pinfunction "1_1") (pintype "passive"))
      (node (ref "U3") (pin "71") (pinfunction "Vcap_1_71") (pintype "passive"))
    )
    (net (code "59") (name "Net-(U3-Vcap_2)") (class "Default")
      (node (ref "C31") (pin "1") (pinfunction "1_1") (pintype "passive"))
      (node (ref "U3") (pin "106") (pinfunction "Vcap_2_106") (pintype "passive"))
    )
    (net (code "60") (name "Net-(U4-REGOUT)") (class "Default")
      (node (ref "C17") (pin "1") (pinfunction "1_1") (pintype "passive"))
      (node (ref "U4") (pin "10") (pinfunction "REGOUT_10") (pintype "passive"))
    )
    (net (code "61") (name "Net-(U4-VDD)") (class "Default")
      (node (ref "C18") (pin "2") (pinfunction "2_2") (pintype "passive"))
      (node (ref "C19") (pin "2") (pinfunction "2_2") (pintype "passive"))
      (node (ref "C20") (pin "2") (pinfunction "2_2") (pintype "passive"))
      (node (ref "FB1") (pin "1") (pintype "passive"))
      (node (ref "U4") (pin "13") (pinfunction "VDD_13") (pintype "passive"))
      (node (ref "U4") (pin "8") (pinfunction "VDDIO_8") (pintype "passive"))
    )
    (net (code "62") (name "Net-(U5-Y)") (class "Default")
      (node (ref "P3") (pin "3") (pinfunction "3_3") (pintype "passive"))
      (node (ref "U5") (pin "4") (pinfunction "Y_4") (pintype "passive"))
    )
    (net (code "63") (name "Net-(U6-A)") (class "Default")
      (node (ref "P5") (pin "3") (pinfunction "3_3") (pintype "passive"))
      (node (ref "U6") (pin "2") (pinfunction "A_2") (pintype "passive"))
    )
    (net (code "64") (name "VCC5V") (class "Default")
      (node (ref "C35") (pin "1") (pinfunction "1_1") (pintype "passive"))
      (node (ref "P5") (pin "2") (pinfunction "2_2") (pintype "passive"))
    )
    (net (code "65") (name "VCC33C") (class "Default")
      (node (ref "C1") (pin "2") (pinfunction "2_2") (pintype "passive"))
      (node (ref "C3") (pin "1") (pinfunction "1_1") (pintype "passive"))
      (node (ref "C53") (pin "2") (pinfunction "2_2") (pintype "passive"))
      (node (ref "C54") (pin "2") (pinfunction "2_2") (pintype "passive"))
      (node (ref "P12") (pin "1") (pinfunction "1_1") (pintype "passive"))
      (node (ref "P13") (pin "1") (pinfunction "1_1") (pintype "passive"))
      (node (ref "P14") (pin "8") (pinfunction "8_8") (pintype "passive"))
      (node (ref "U1") (pin "1") (pinfunction "1_1") (pintype "passive"))
    )
    (net (code "66") (name "VCC33P") (class "Default")
      (node (ref "C10") (pin "2") (pinfunction "2_2") (pintype "passive"))
      (node (ref "C11") (pin "2") (pinfunction "2_2") (pintype "passive"))
      (node (ref "C12") (pin "2") (pinfunction "2_2") (pintype "passive"))
      (node (ref "C13") (pin "2") (pinfunction "2_2") (pintype "passive"))
      (node (ref "C14") (pin "2") (pinfunction "2_2") (pintype "passive"))
      (node (ref "C15") (pin "2") (pinfunction "2_2") (pintype "passive"))
      (node (ref "C16") (pin "2") (pinfunction "2_2") (pintype "passive"))
      (node (ref "C2") (pin "2") (pinfunction "2_2") (pintype "passive"))
      (node (ref "C22") (pin "2") (pinfunction "2_2") (pintype "passive"))
      (node (ref "C27") (pin "2") (pinfunction "2_2") (pintype "passive"))
      (node (ref "C36") (pin "1") (pinfunction "1_1") (pintype "passive"))
      (node (ref "C4") (pin "2") (pinfunction "2_2") (pintype "passive"))
      (node (ref "C5") (pin "2") (pinfunction "2_2") (pintype "passive"))
      (node (ref "C6") (pin "2") (pinfunction "2_2") (pintype "passive"))
      (node (ref "C7") (pin "2") (pinfunction "2_2") (pintype "passive"))
      (node (ref "C8") (pin "2") (pinfunction "2_2") (pintype "passive"))
      (node (ref "C9") (pin "2") (pinfunction "2_2") (pintype "passive"))
      (node (ref "FB1") (pin "2") (pintype "passive"))
      (node (ref "J1") (pin "2") (pintype "passive"))
      (node (ref "J2") (pin "2") (pintype "passive"))
      (node (ref "P1") (pin "1") (pinfunction "1_1") (pintype "passive"))
      (node (ref "P15") (pin "8") (pinfunction "8_8") (pintype "passive"))
      (node (ref "R13") (pin "1") (pinfunction "1_1") (pintype "passive"))
      (node (ref "R14") (pin "1") (pinfunction "1_1") (pintype "passive"))
      (node (ref "R3") (pin "1") (pinfunction "1_1") (pintype "passive"))
      (node (ref "R4") (pin "1") (pinfunction "1_1") (pintype "passive"))
      (node (ref "R5") (pin "1") (pinfunction "1_1") (pintype "passive"))
      (node (ref "R6") (pin "1") (pinfunction "1_1") (pintype "passive"))
      (node (ref "U2") (pin "8") (pinfunction "VCC1_8") (pintype "passive"))
      (node (ref "U3") (pin "108") (pinfunction "VDD_108") (pintype "passive"))
      (node (ref "U3") (pin "121") (pinfunction "VDD_121") (pintype "passive"))
      (node (ref "U3") (pin "131") (pinfunction "VDD_131") (pintype "passive"))
      (node (ref "U3") (pin "143") (pinfunction "PDR_ON_143") (pintype "passive"))
      (node (ref "U3") (pin "144") (pinfunction "VDD_144") (pintype "passive"))
      (node (ref "U3") (pin "17") (pinfunction "VDD_17") (pintype "passive"))
      (node (ref "U3") (pin "30") (pinfunction "VDD_30") (pintype "passive"))
      (node (ref "U3") (pin "39") (pinfunction "VDD_39") (pintype "passive"))
      (node (ref "U3") (pin "52") (pinfunction "VDD_52") (pintype "passive"))
      (node (ref "U3") (pin "6") (pinfunction "VBAT_6") (pintype "passive"))
      (node (ref "U3") (pin "62") (pinfunction "VDD_62") (pintype "passive"))
      (node (ref "U3") (pin "72") (pinfunction "VDD_72") (pintype "passive"))
      (node (ref "U3") (pin "84") (pinfunction "VDD_84") (pintype "passive"))
      (node (ref "U3") (pin "95") (pinfunction "VDD_95") (pintype "passive"))
      (node (ref "U5") (pin "5") (pinfunction "VCC_5") (pintype "passive"))
      (node (ref "U6") (pin "5") (pinfunction "VCC_5") (pintype "passive"))
    )
    (net (code "67") (name "unconnected-(P3-Pad2)") (class "Default")
      (node (ref "P3") (pin "2") (pinfunction "2_2") (pintype "passive+no_connect"))
    )
    (net (code "68") (name "unconnected-(P4-Pad1)") (class "Default")
      (node (ref "P4") (pin "1") (pinfunction "1_1") (pintype "passive+no_connect"))
    )
    (net (code "69") (name "unconnected-(U3-PA0-WKUP{slash}U2_CTS{slash}U4_TX{slash}ETH_MII_CRS{slash}TIM2_CH1_ETR{slash}TIM5_CH1{slash}TIM8_ETR{slash}ADC123_IN0-Pad34)") (class "Default")
      (node (ref "U3") (pin "34") (pinfunction "PA0-WKUP/U2_CTS/U4_TX/ETH_MII_CRS/TIM2_CH1_ETR/TIM5_CH1/TIM8_ETR/ADC123_IN0_34") (pintype "passive"))
    )
    (net (code "70") (name "unconnected-(U3-PA1{slash}U2_RTS{slash}U4_RX{slash}ETH_RMII_REF_CLK{slash}ETH_MII_RX_CLK{slash}TIM2_CH2{slash}TIM5_CH2{slash}ADC123_IN1-Pad35)") (class "Default")
      (node (ref "U3") (pin "35") (pinfunction "PA1/U2_RTS/U4_RX/ETH_RMII_REF_CLK/ETH_MII_RX_CLK/TIM2_CH2/TIM5_CH2/ADC123_IN1_35") (pintype "passive"))
    )
    (net (code "71") (name "unconnected-(U3-PA2{slash}U2_TX{slash}TIM2_CH3{slash}TIM5_CH3{slash}TIM9_CH1{slash}ETH_MDIO{slash}ADC123_IN2-Pad36)") (class "Default")
      (node (ref "U3") (pin "36") (pinfunction "PA2/U2_TX/TIM2_CH3/TIM5_CH3/TIM9_CH1/ETH_MDIO/ADC123_IN2_36") (pintype "passive"))
    )
    (net (code "72") (name "unconnected-(U3-PA8{slash}TIM1_CH1{slash}U1_CK{slash}I2C3_SCL{slash}MCO1{slash}OTG_FS_SOF-Pad100)") (class "Default")
      (node (ref "U3") (pin "100") (pinfunction "PA8/TIM1_CH1/U1_CK/I2C3_SCL/MCO1/OTG_FS_SOF_100") (pintype "passive"))
    )
    (net (code "73") (name "unconnected-(U3-PA11{slash}TIM1_CH4{slash}U1_CTS{slash}CAN1_RX{slash}OTG_FS_DM-Pad103)") (class "Default")
      (node (ref "U3") (pin "103") (pinfunction "PA11/TIM1_CH4/U1_CTS/CAN1_RX/OTG_FS_DM_103") (pintype "passive"))
    )
    (net (code "74") (name "unconnected-(U3-PA12{slash}TIM1_ETR{slash}U1_RTS{slash}CAN1_TX{slash}OTG_FS_DP-Pad104)") (class "Default")
      (node (ref "U3") (pin "104") (pinfunction "PA12/TIM1_ETR/U1_RTS/CAN1_TX/OTG_FS_DP_104") (pintype "passive"))
    )
    (net (code "75") (name "unconnected-(U3-PA15{slash}JTDI{slash}SPI1_NSS{slash}SPI3_NSS{slash}TIM2_CH1_ETR{slash}I2S3_WS-Pad110)") (class "Default")
      (node (ref "U3") (pin "110") (pinfunction "PA15/JTDI/SPI1_NSS/SPI3_NSS/TIM2_CH1_ETR/I2S3_WS_110") (pintype "passive"))
    )
    (net (code "76") (name "unconnected-(U3-PB0{slash}TIM1_CH2N{slash}TIM3_CH3{slash}TIM8_CH2N{slash}OTG_HS_ULPI_D1{slash}ETH_MII_RXD2{slash}ADC12_IN8-Pad46)") (class "Default")
      (node (ref "U3") (pin "46") (pinfunction "PB0/TIM1_CH2N/TIM3_CH3/TIM8_CH2N/OTG_HS_ULPI_D1/ETH_MII_RXD2/ADC12_IN8_46") (pintype "passive"))
    )
    (net (code "77") (name "unconnected-(U3-PB1{slash}TIM1_CH3N{slash}TIM3_CH4{slash}TIM8_CH3N{slash}OTG_HS_INTN{slash}ETH_MII_RXD3{slash}ADC12_IN9-Pad47)") (class "Default")
      (node (ref "U3") (pin "47") (pinfunction "PB1/TIM1_CH3N/TIM3_CH4/TIM8_CH3N/OTG_HS_INTN/ETH_MII_RXD3/ADC12_IN9_47") (pintype "passive"))
    )
    (net (code "78") (name "unconnected-(U3-PB3{slash}JTDO{slash}TRACESWO{slash}TIM2_CH2{slash}SPI1_SCK{slash}SPI3_SCK{slash}I2S3_CK-Pad133)") (class "Default")
      (node (ref "U3") (pin "133") (pinfunction "PB3/JTDO/TRACESWO/TIM2_CH2/SPI1_SCK/SPI3_SCK/I2S3_CK_133") (pintype "passive"))
    )
    (net (code "79") (name "unconnected-(U3-PB4{slash}JNTRST{slash}TIM3_CH1{slash}SPI1_MISO{slash}SPI3_MISO{slash}I2S3ext_SD-Pad134)") (class "Default")
      (node (ref "U3") (pin "134") (pinfunction "PB4/JNTRST/TIM3_CH1/SPI1_MISO/SPI3_MISO/I2S3ext_SD_134") (pintype "passive"))
    )
    (net (code "80") (name "unconnected-(U3-PB9{slash}TIM4_CH4{slash}TIM11_CH1{slash}CAN1_TX{slash}SDIO_D5{slash}SPI2_NSS{slash}I2C1_SDA{slash}DCMI_D7{slash}I2S2_WS-Pad140)") (class "Default")
      (node (ref "U3") (pin "140") (pinfunction "PB9/TIM4_CH4/TIM11_CH1/CAN1_TX/SDIO_D5/SPI2_NSS/I2C1_SDA/DCMI_D7/I2S2_WS_140") (pintype "passive"))
    )
    (net (code "81") (name "unconnected-(U3-PC0{slash}OTG_HS_ULPI_STP{slash}ADC123_IN10-Pad26)") (class "Default")
      (node (ref "U3") (pin "26") (pinfunction "PC0/OTG_HS_ULPI_STP/ADC123_IN10_26") (pintype "passive"))
    )
    (net (code "82") (name "unconnected-(U3-PC1{slash}ETH_MDC{slash}ADC123_IN11-Pad27)") (class "Default")
      (node (ref "U3") (pin "27") (pinfunction "PC1/ETH_MDC/ADC123_IN11_27") (pintype "passive"))
    )
    (net (code "83") (name "unconnected-(U3-PC2{slash}SPI2_MISO{slash}OTG_HS_ULPI_DIR{slash}ETH_MII_TXD2{slash}I2S2ext_SD{slash}ADC123_IN12-Pad28)") (class "Default")
      (node (ref "U3") (pin "28") (pinfunction "PC2/SPI2_MISO/OTG_HS_ULPI_DIR/ETH_MII_TXD2/I2S2ext_SD/ADC123_IN12_28") (pintype "passive"))
    )
    (net (code "84") (name "unconnected-(U3-PC3{slash}SPI2_MOSI{slash}OTG_HS_ULPI_NXT{slash}ETH_MII_TX_CLK{slash}I2S2_SD{slash}ADC123_IN13-Pad29)") (class "Default")
      (node (ref "U3") (pin "29") (pinfunction "PC3/SPI2_MOSI/OTG_HS_ULPI_NXT/ETH_MII_TX_CLK/I2S2_SD/ADC123_IN13_29") (pintype "passive"))
    )
    (net (code "85") (name "unconnected-(U3-PC6{slash}TIM3_CH1{slash}TIM8_CH1{slash}U6_TX{slash}SDIO_D6{slash}DCMI_D0{slash}I2S2_MCK-Pad96)") (class "Default")
      (node (ref "U3") (pin "96") (pinfunction "PC6/TIM3_CH1/TIM8_CH1/U6_TX/SDIO_D6/DCMI_D0/I2S2_MCK_96") (pintype "passive"))
    )
    (net (code "86") (name "unconnected-(U3-PC7{slash}TIM3_CH2{slash}TIM8_CH2{slash}U6_RX{slash}SDIO_D7{slash}DCMI_D1{slash}I2S3_MCK-Pad97)") (class "Default")
      (node (ref "U3") (pin "97") (pinfunction "PC7/TIM3_CH2/TIM8_CH2/U6_RX/SDIO_D7/DCMI_D1/I2S3_MCK_97") (pintype "passive"))
    )
    (net (code "87") (name "unconnected-(U3-PC8{slash}TIM3_CH3{slash}TIM8_CH3{slash}U6_CK{slash}SDIO_D0{slash}DCMI_D2-Pad98)") (class "Default")
      (node (ref "U3") (pin "98") (pinfunction "PC8/TIM3_CH3/TIM8_CH3/U6_CK/SDIO_D0/DCMI_D2_98") (pintype "passive"))
    )
    (net (code "88") (name "unconnected-(U3-PC9{slash}TIM3_CH4{slash}TIM8_CH4{slash}I2C3_SDA{slash}SDIO_D1{slash}DCMI_D3{slash}MCO2{slash}I2S_CKIN-Pad99)") (class "Default")
      (node (ref "U3") (pin "99") (pinfunction "PC9/TIM3_CH4/TIM8_CH4/I2C3_SDA/SDIO_D1/DCMI_D3/MCO2/I2S_CKIN_99") (pintype "passive"))
    )
    (net (code "89") (name "unconnected-(U3-PC13{slash}RTC_AF1-Pad7)") (class "Default")
      (node (ref "U3") (pin "7") (pinfunction "PC13/RTC_AF1_7") (pintype "passive"))
    )
    (net (code "90") (name "unconnected-(U3-PD3{slash}FSMC_CLK{slash}U2_CTS-Pad117)") (class "Default")
      (node (ref "U3") (pin "117") (pinfunction "PD3/FSMC_CLK/U2_CTS_117") (pintype "passive"))
    )
    (net (code "91") (name "unconnected-(U3-PD4{slash}FSMC_NOE{slash}U2_RTS-Pad118)") (class "Default")
      (node (ref "U3") (pin "118") (pinfunction "PD4/FSMC_NOE/U2_RTS_118") (pintype "passive"))
    )
    (net (code "92") (name "unconnected-(U3-PD7{slash}FSMC_NE1{slash}FSMC_NCE2{slash}U2_CK-Pad123)") (class "Default")
      (node (ref "U3") (pin "123") (pinfunction "PD7/FSMC_NE1/FSMC_NCE2/U2_CK_123") (pintype "passive"))
    )
    (net (code "93") (name "unconnected-(U3-PD11{slash}FSMC_A16{slash}FSMC_CLE{slash}U3_CTS-Pad80)") (class "Default")
      (node (ref "U3") (pin "80") (pinfunction "PD11/FSMC_A16/FSMC_CLE/U3_CTS_80") (pintype "passive"))
    )
    (net (code "94") (name "unconnected-(U3-PD13{slash}FSMC_A18{slash}TIM4_CH2-Pad82)") (class "Default")
      (node (ref "U3") (pin "82") (pinfunction "PD13/FSMC_A18/TIM4_CH2_82") (pintype "passive"))
    )
    (net (code "95") (name "unconnected-(U3-PD14{slash}FSMC_D0{slash}TIM4_CH3-Pad85)") (class "Default")
      (node (ref "U3") (pin "85") (pinfunction "PD14/FSMC_D0/TIM4_CH3_85") (pintype "passive"))
    )
    (net (code "96") (name "unconnected-(U3-PD15{slash}FSMC_D1{slash}TIM4_CH4-Pad86)") (class "Default")
      (node (ref "U3") (pin "86") (pinfunction "PD15/FSMC_D1/TIM4_CH4_86") (pintype "passive"))
    )
    (net (code "97") (name "unconnected-(U3-PE0{slash}TIM4_ETR{slash}FSMC_NBL0{slash}DCMI_D2-Pad141)") (class "Default")
      (node (ref "U3") (pin "141") (pinfunction "PE0/TIM4_ETR/FSMC_NBL0/DCMI_D2_141") (pintype "passive"))
    )
    (net (code "98") (name "unconnected-(U3-PE1{slash}FSMC_NBL1{slash}DCMI_D3-Pad142)") (class "Default")
      (node (ref "U3") (pin "142") (pinfunction "PE1/FSMC_NBL1/DCMI_D3_142") (pintype "passive"))
    )
    (net (code "99") (name "unconnected-(U3-PE2{slash}TRACECLK{slash}FSMC_A23{slash}ETH_MII_TXD3-Pad1)") (class "Default")
      (node (ref "U3") (pin "1") (pinfunction "PE2/TRACECLK/FSMC_A23/ETH_MII_TXD3_1") (pintype "passive"))
    )
    (net (code "100") (name "unconnected-(U3-PE3{slash}TRACED0{slash}FSMC_A19-Pad2)") (class "Default")
      (node (ref "U3") (pin "2") (pinfunction "PE3/TRACED0/FSMC_A19_2") (pintype "passive"))
    )
    (net (code "101") (name "unconnected-(U3-PE4{slash}TRACED1{slash}FSMC_A20{slash}DCMI_D4-Pad3)") (class "Default")
      (node (ref "U3") (pin "3") (pinfunction "PE4/TRACED1/FSMC_A20/DCMI_D4_3") (pintype "passive"))
    )
    (net (code "102") (name "unconnected-(U3-PE5{slash}TRACED2{slash}FSMC_A21{slash}TIM9_CH1{slash}DCMI_D6-Pad4)") (class "Default")
      (node (ref "U3") (pin "4") (pinfunction "PE5/TRACED2/FSMC_A21/TIM9_CH1/DCMI_D6_4") (pintype "passive"))
    )
    (net (code "103") (name "unconnected-(U3-PE6{slash}TRACED3{slash}FSMC_A22{slash}TIM9_CH2{slash}DCMI_D7-Pad5)") (class "Default")
      (node (ref "U3") (pin "5") (pinfunction "PE6/TRACED3/FSMC_A22/TIM9_CH2/DCMI_D7_5") (pintype "passive"))
    )
    (net (code "104") (name "unconnected-(U3-PE7{slash}FSMC_D4{slash}TIM1_ETR-Pad58)") (class "Default")
      (node (ref "U3") (pin "58") (pinfunction "PE7/FSMC_D4/TIM1_ETR_58") (pintype "passive"))
    )
    (net (code "105") (name "unconnected-(U3-PE8{slash}FSMC_D5{slash}TIM1_CH1N-Pad59)") (class "Default")
      (node (ref "U3") (pin "59") (pinfunction "PE8/FSMC_D5/TIM1_CH1N_59") (pintype "passive"))
    )
    (net (code "106") (name "unconnected-(U3-PE9{slash}FSMC_D6{slash}TIM1_CH1-Pad60)") (class "Default")
      (node (ref "U3") (pin "60") (pinfunction "PE9/FSMC_D6/TIM1_CH1_60") (pintype "passive"))
    )
    (net (code "107") (name "unconnected-(U3-PE10{slash}FSMC_D7{slash}TIM1_CH2N-Pad63)") (class "Default")
      (node (ref "U3") (pin "63") (pinfunction "PE10/FSMC_D7/TIM1_CH2N_63") (pintype "passive"))
    )
    (net (code "108") (name "unconnected-(U3-PE11{slash}FSMC_D8{slash}TIM1_CH2-Pad64)") (class "Default")
      (node (ref "U3") (pin "64") (pinfunction "PE11/FSMC_D8/TIM1_CH2_64") (pintype "passive"))
    )
    (net (code "109") (name "unconnected-(U3-PE12{slash}FSMC_D9{slash}TIM1_CH3N-Pad65)") (class "Default")
      (node (ref "U3") (pin "65") (pinfunction "PE12/FSMC_D9/TIM1_CH3N_65") (pintype "passive"))
    )
    (net (code "110") (name "unconnected-(U3-PE13{slash}FSMC_D10{slash}TIM1_CH3-Pad66)") (class "Default")
      (node (ref "U3") (pin "66") (pinfunction "PE13/FSMC_D10/TIM1_CH3_66") (pintype "passive"))
    )
    (net (code "111") (name "unconnected-(U3-PE14{slash}FSMC_D11{slash}TIM1_CH4-Pad67)") (class "Default")
      (node (ref "U3") (pin "67") (pinfunction "PE14/FSMC_D11/TIM1_CH4_67") (pintype "passive"))
    )
    (net (code "112") (name "unconnected-(U3-PE15{slash}FSMC_D12{slash}TIM1_BKIN-Pad68)") (class "Default")
      (node (ref "U3") (pin "68") (pinfunction "PE15/FSMC_D12/TIM1_BKIN_68") (pintype "passive"))
    )
    (net (code "113") (name "unconnected-(U3-PF2{slash}FSMC_A2{slash}I2C2_SMBA-Pad12)") (class "Default")
      (node (ref "U3") (pin "12") (pinfunction "PF2/FSMC_A2/I2C2_SMBA_12") (pintype "passive"))
    )
    (net (code "114") (name "unconnected-(U3-PF3{slash}FSMC_A3{slash}ADC3_IN9-Pad13)") (class "Default")
      (node (ref "U3") (pin "13") (pinfunction "PF3/FSMC_A3/ADC3_IN9_13") (pintype "passive"))
    )
    (net (code "115") (name "unconnected-(U3-PF4{slash}FSMC_A4{slash}ADC3_IN14-Pad14)") (class "Default")
      (node (ref "U3") (pin "14") (pinfunction "PF4/FSMC_A4/ADC3_IN14_14") (pintype "passive"))
    )
    (net (code "116") (name "unconnected-(U3-PF5{slash}FSMC_A5{slash}ADC3_IN15-Pad15)") (class "Default")
      (node (ref "U3") (pin "15") (pinfunction "PF5/FSMC_A5/ADC3_IN15_15") (pintype "passive"))
    )
    (net (code "117") (name "unconnected-(U3-PF6{slash}TIM10_CH1{slash}FSMC_NIORD{slash}ADC3_IN4-Pad18)") (class "Default")
      (node (ref "U3") (pin "18") (pinfunction "PF6/TIM10_CH1/FSMC_NIORD/ADC3_IN4_18") (pintype "passive"))
    )
    (net (code "118") (name "unconnected-(U3-PF7{slash}TIM11_CH1{slash}FSMC_NREG{slash}ADC3_IN5-Pad19)") (class "Default")
      (node (ref "U3") (pin "19") (pinfunction "PF7/TIM11_CH1/FSMC_NREG/ADC3_IN5_19") (pintype "passive"))
    )
    (net (code "119") (name "unconnected-(U3-PF8{slash}TIM13_CH1{slash}FSMC_NIOWR{slash}ADC3_IN6-Pad20)") (class "Default")
      (node (ref "U3") (pin "20") (pinfunction "PF8/TIM13_CH1/FSMC_NIOWR/ADC3_IN6_20") (pintype "passive"))
    )
    (net (code "120") (name "unconnected-(U3-PF9{slash}TIM14_CH1{slash}FSMC_CD{slash}ADC3_IN7-Pad21)") (class "Default")
      (node (ref "U3") (pin "21") (pinfunction "PF9/TIM14_CH1/FSMC_CD/ADC3_IN7_21") (pintype "passive"))
    )
    (net (code "121") (name "unconnected-(U3-PF10{slash}FSMC_INTR{slash}ADC3_IN8-Pad22)") (class "Default")
      (node (ref "U3") (pin "22") (pinfunction "PF10/FSMC_INTR/ADC3_IN8_22") (pintype "passive"))
    )
    (net (code "122") (name "unconnected-(U3-PF11{slash}DCMI_D12-Pad49)") (class "Default")
      (node (ref "U3") (pin "49") (pinfunction "PF11/DCMI_D12_49") (pintype "passive"))
    )
    (net (code "123") (name "unconnected-(U3-PF13{slash}FSMC_A7-Pad53)") (class "Default")
      (node (ref "U3") (pin "53") (pinfunction "PF13/FSMC_A7_53") (pintype "passive"))
    )
    (net (code "124") (name "unconnected-(U3-PF14{slash}FSMC_A8-Pad54)") (class "Default")
      (node (ref "U3") (pin "54") (pinfunction "PF14/FSMC_A8_54") (pintype "passive"))
    )
    (net (code "125") (name "unconnected-(U3-PF15{slash}FSMC_A9-Pad55)") (class "Default")
      (node (ref "U3") (pin "55") (pinfunction "PF15/FSMC_A9_55") (pintype "passive"))
    )
    (net (code "126") (name "unconnected-(U3-PG0{slash}FSMC_A10-Pad56)") (class "Default")
      (node (ref "U3") (pin "56") (pinfunction "PG0/FSMC_A10_56") (pintype "passive"))
    )
    (net (code "127") (name "unconnected-(U3-PG1{slash}FSMC_A11-Pad57)") (class "Default")
      (node (ref "U3") (pin "57") (pinfunction "PG1/FSMC_A11_57") (pintype "passive"))
    )
    (net (code "128") (name "unconnected-(U3-PG2{slash}FSMC_A12-Pad87)") (class "Default")
      (node (ref "U3") (pin "87") (pinfunction "PG2/FSMC_A12_87") (pintype "passive"))
    )
    (net (code "129") (name "unconnected-(U3-PG3{slash}FSMC_A13-Pad88)") (class "Default")
      (node (ref "U3") (pin "88") (pinfunction "PG3/FSMC_A13_88") (pintype "passive"))
    )
    (net (code "130") (name "unconnected-(U3-PG4{slash}FSMC_A14-Pad89)") (class "Default")
      (node (ref "U3") (pin "89") (pinfunction "PG4/FSMC_A14_89") (pintype "passive"))
    )
    (net (code "131") (name "unconnected-(U3-PG5{slash}FSMC_A15-Pad90)") (class "Default")
      (node (ref "U3") (pin "90") (pinfunction "PG5/FSMC_A15_90") (pintype "passive"))
    )
    (net (code "132") (name "unconnected-(U3-PG6{slash}FSMC_INT2-Pad91)") (class "Default")
      (node (ref "U3") (pin "91") (pinfunction "PG6/FSMC_INT2_91") (pintype "passive"))
    )
    (net (code "133") (name "unconnected-(U3-PG7{slash}FSMC_INT3{slash}U6_CK-Pad92)") (class "Default")
      (node (ref "U3") (pin "92") (pinfunction "PG7/FSMC_INT3/U6_CK_92") (pintype "passive"))
    )
    (net (code "134") (name "unconnected-(U3-PG8{slash}U6_RTS{slash}ETH_PPS_OUT-Pad93)") (class "Default")
      (node (ref "U3") (pin "93") (pinfunction "PG8/U6_RTS/ETH_PPS_OUT_93") (pintype "passive"))
    )
    (net (code "135") (name "unconnected-(U3-PG10{slash}FSMC_NCE4_1{slash}FSMC_NE3-Pad125)") (class "Default")
      (node (ref "U3") (pin "125") (pinfunction "PG10/FSMC_NCE4_1/FSMC_NE3_125") (pintype "passive"))
    )
    (net (code "136") (name "unconnected-(U3-PG11{slash}FSMC_NCE4_2{slash}ETH_MII_TX_EN{slash}ETH_RMII_TX_EN-Pad126)") (class "Default")
      (node (ref "U3") (pin "126") (pinfunction "PG11/FSMC_NCE4_2/ETH_MII_TX_EN/ETH_RMII_TX_EN_126") (pintype "passive"))
    )
    (net (code "137") (name "unconnected-(U3-PG13{slash}FSMC_A24{slash}U6_CTS{slash}ETH_MII_TXD0{slash}ETH_RMII_TXD0-Pad128)") (class "Default")
      (node (ref "U3") (pin "128") (pinfunction "PG13/FSMC_A24/U6_CTS/ETH_MII_TXD0/ETH_RMII_TXD0_128") (pintype "passive"))
    )
    (net (code "138") (name "unconnected-(U3-PG15{slash}U6_CTS{slash}DCMI_D13-Pad132)") (class "Default")
      (node (ref "U3") (pin "132") (pinfunction "PG15/U6_CTS/DCMI_D13_132") (pintype "passive"))
    )
    (net (code "139") (name "unconnected-(U4-AUX_CL-Pad7)") (class "Default")
      (node (ref "U4") (pin "7") (pinfunction "AUX_CL_7") (pintype "passive+no_connect"))
    )
    (net (code "140") (name "unconnected-(U4-AUX_DA-Pad21)") (class "Default")
      (node (ref "U4") (pin "21") (pinfunction "AUX_DA_21") (pintype "passive+no_connect"))
    )
    (net (code "141") (name "unconnected-(U4-NC-Pad1)") (class "Default")
      (node (ref "U4") (pin "1") (pinfunction "NC_1") (pintype "passive+no_connect"))
    )
    (net (code "142") (name "unconnected-(U4-NC-Pad2)") (class "Default")
      (node (ref "U4") (pin "2") (pinfunction "NC_2") (pintype "passive+no_connect"))
    )
    (net (code "143") (name "unconnected-(U4-NC-Pad3)") (class "Default")
      (node (ref "U4") (pin "3") (pinfunction "NC_3") (pintype "passive+no_connect"))
    )
    (net (code "144") (name "unconnected-(U4-NC-Pad4)") (class "Default")
      (node (ref "U4") (pin "4") (pinfunction "NC_4") (pintype "passive+no_connect"))
    )
    (net (code "145") (name "unconnected-(U4-NC-Pad5)") (class "Default")
      (node (ref "U4") (pin "5") (pinfunction "NC_5") (pintype "passive+no_connect"))
    )
    (net (code "146") (name "unconnected-(U4-NC-Pad6)") (class "Default")
      (node (ref "U4") (pin "6") (pinfunction "NC_6") (pintype "passive+no_connect"))
    )
    (net (code "147") (name "unconnected-(U4-NC-Pad14)") (class "Default")
      (node (ref "U4") (pin "14") (pinfunction "NC_14") (pintype "passive+no_connect"))
    )
    (net (code "148") (name "unconnected-(U4-NC-Pad15)") (class "Default")
      (node (ref "U4") (pin "15") (pinfunction "NC_15") (pintype "passive+no_connect"))
    )
    (net (code "149") (name "unconnected-(U4-NC-Pad16)") (class "Default")
      (node (ref "U4") (pin "16") (pinfunction "NC_16") (pintype "passive+no_connect"))
    )
    (net (code "150") (name "unconnected-(U4-NC-Pad17)") (class "Default")
      (node (ref "U4") (pin "17") (pinfunction "NC_17") (pintype "passive+no_connect"))
    )
    (net (code "151") (name "unconnected-(U4-RESV-Pad19)") (class "Default")
      (node (ref "U4") (pin "19") (pinfunction "RESV_19") (pintype "passive+no_connect"))
    )
    (net (code "152") (name "unconnected-(U5-NC-Pad1)") (class "Default")
      (node (ref "U5") (pin "1") (pinfunction "NC_1") (pintype "passive+no_connect"))
    )
    (net (code "153") (name "unconnected-(U6-NC-Pad1)") (class "Default")
      (node (ref "U6") (pin "1") (pinfunction "NC_1") (pintype "passive+no_connect"))
    )
  )
)
